# source_eagle.net
KiCad netlist of a schematic drawn in EAGLE
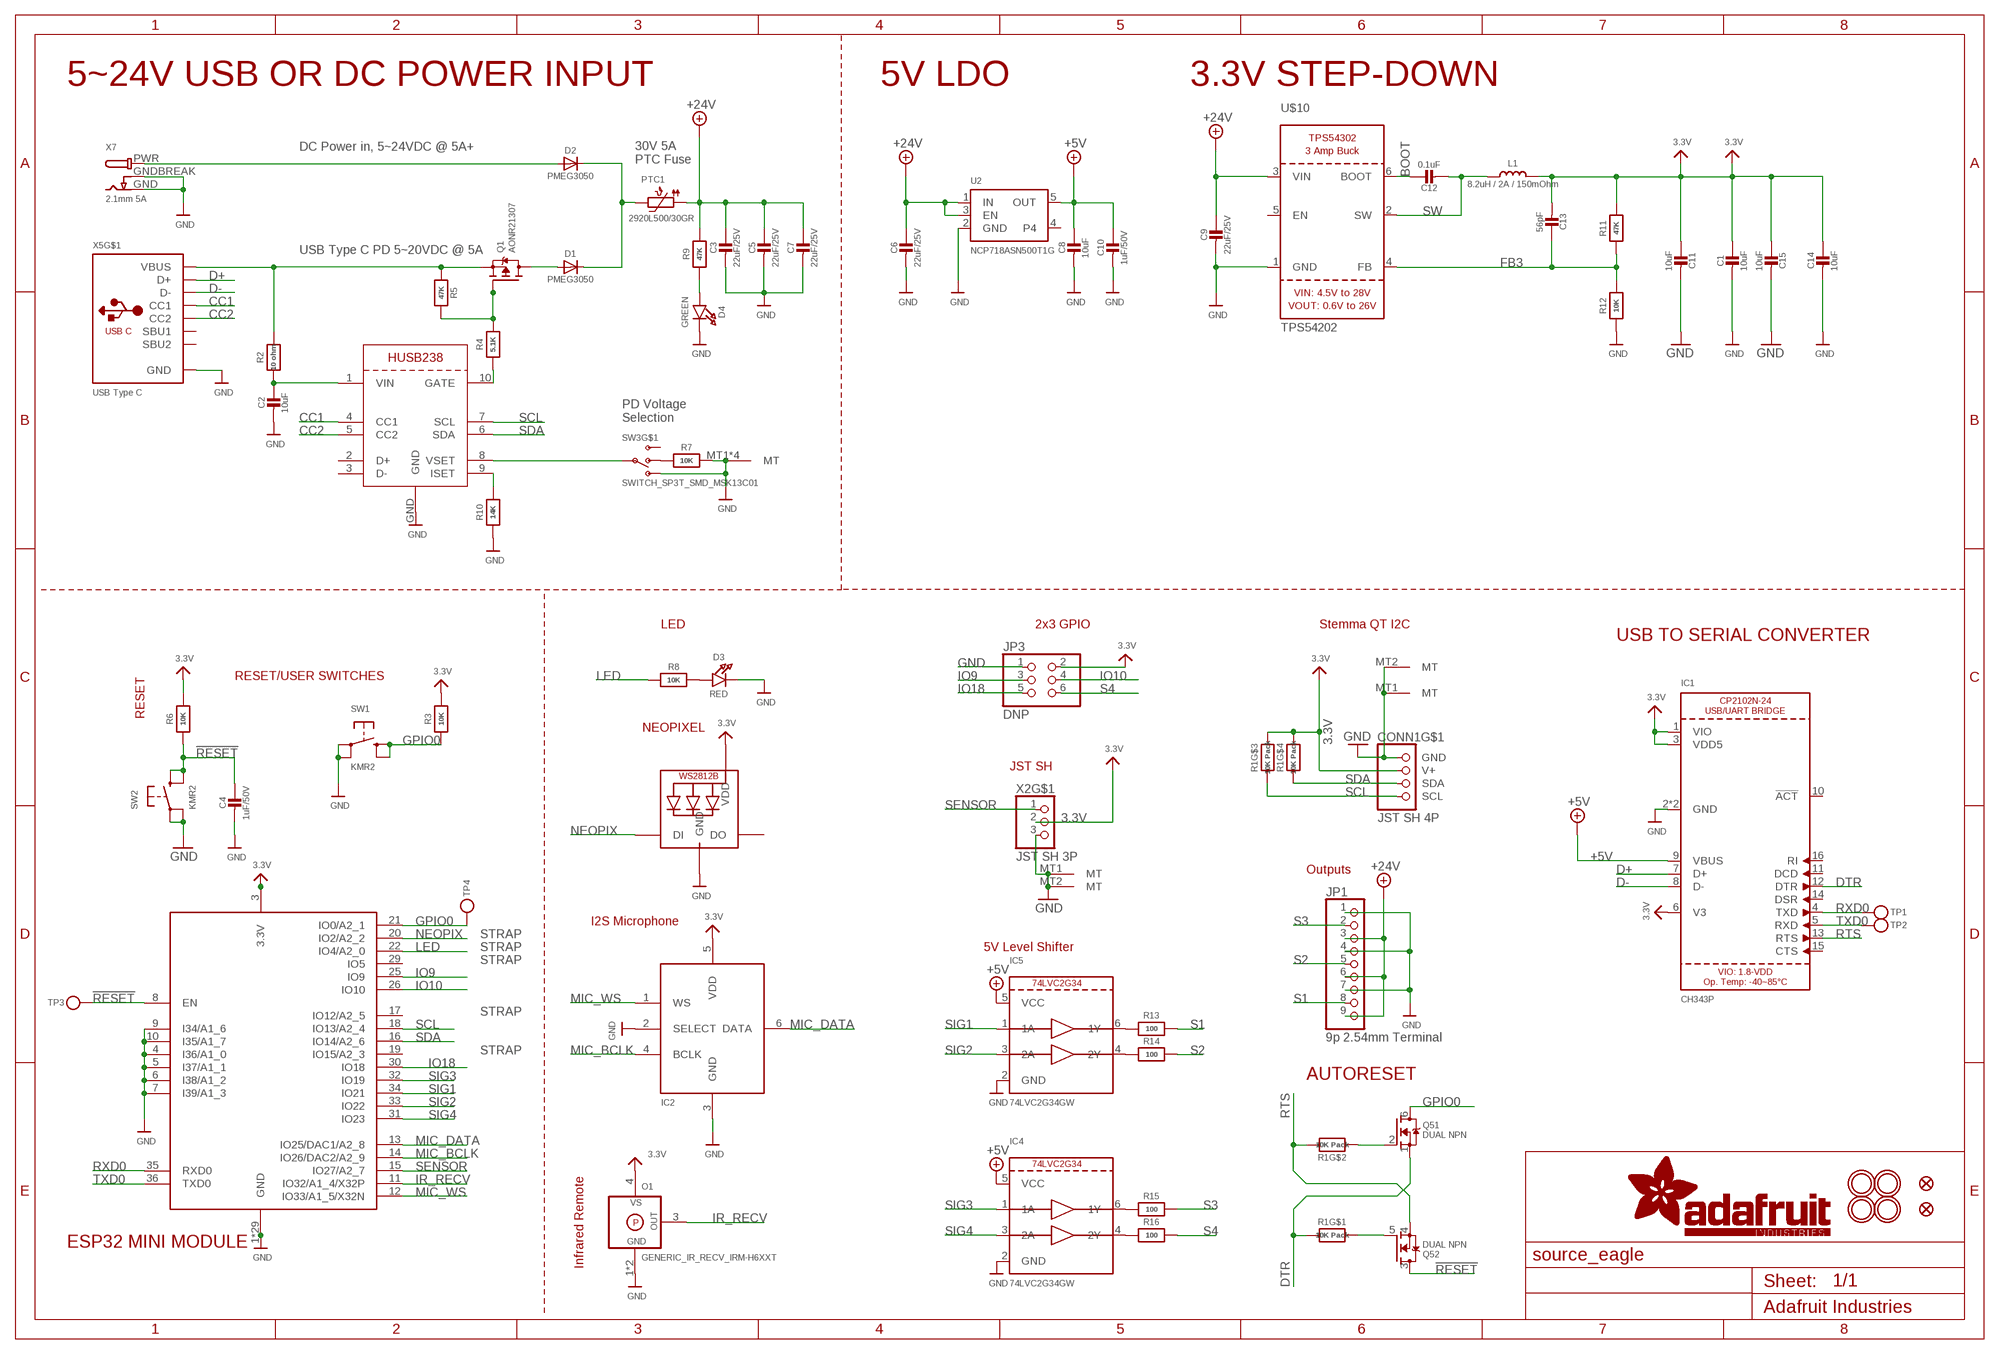
[diagram p0: schematic, sheet 1]

(export (version "E")
  (design (tool "Eeschema 10.0.6"))
  (components
    (comp (ref "C1")
      (value "10uF")
      (footprint "eagle-import:0805-NO")
      (libsource (lib "eagle-import") (part "CAP_CERAMIC0805-NOOUTLINE"))
    )
    (comp (ref "C2")
      (value "10uF")
      (footprint "eagle-import:0805-NO")
      (libsource (lib "eagle-import") (part "CAP_CERAMIC0805-NOOUTLINE"))
    )
    (comp (ref "C3")
      (value "22uF/25V")
      (footprint "eagle-import:0805-NO")
      (libsource (lib "eagle-import") (part "CAP_CERAMIC0805-NOOUTLINE"))
    )
    (comp (ref "C4")
      (value "1uF/50V")
      (footprint "eagle-import:0603-NO")
      (libsource (lib "eagle-import") (part "CAP_CERAMIC0603_NO"))
    )
    (comp (ref "C5")
      (value "22uF/25V")
      (footprint "eagle-import:0805-NO")
      (libsource (lib "eagle-import") (part "CAP_CERAMIC0805-NOOUTLINE"))
    )
    (comp (ref "C6")
      (value "22uF/25V")
      (footprint "eagle-import:0805-NO")
      (libsource (lib "eagle-import") (part "CAP_CERAMIC0805-NOOUTLINE"))
    )
    (comp (ref "C7")
      (value "22uF/25V")
      (footprint "eagle-import:0805-NO")
      (libsource (lib "eagle-import") (part "CAP_CERAMIC0805-NOOUTLINE"))
    )
    (comp (ref "C8")
      (value "10uF")
      (footprint "eagle-import:0805-NO")
      (fields (field (name "REV") "D"))
      (libsource (lib "eagle-import") (part "CAP_CERAMIC0805-NOOUTLINE"))
    )
    (comp (ref "C9")
      (value "22uF/25V")
      (footprint "eagle-import:0805-NO")
      (libsource (lib "eagle-import") (part "CAP_CERAMIC0805-NOOUTLINE"))
    )
    (comp (ref "C10")
      (value "1uF/50V")
      (footprint "eagle-import:0603-NO")
      (libsource (lib "eagle-import") (part "CAP_CERAMIC0603_NO"))
    )
    (comp (ref "C11")
      (value "10uF")
      (footprint "eagle-import:0805-NO")
      (libsource (lib "eagle-import") (part "CAP_CERAMIC0805-NOOUTLINE"))
    )
    (comp (ref "C12")
      (value "0.1uF")
      (footprint "eagle-import:0603-NO")
      (libsource (lib "eagle-import") (part "CAP_CERAMIC0603_NO"))
    )
    (comp (ref "C13")
      (value "56pF")
      (footprint "eagle-import:0603-NO")
      (libsource (lib "eagle-import") (part "CAP_CERAMIC0603_NO"))
    )
    (comp (ref "C14")
      (value "10uF")
      (footprint "eagle-import:0805-NO")
      (libsource (lib "eagle-import") (part "CAP_CERAMIC0805-NOOUTLINE"))
    )
    (comp (ref "C15")
      (value "10uF")
      (footprint "eagle-import:0805-NO")
      (libsource (lib "eagle-import") (part "CAP_CERAMIC0805-NOOUTLINE"))
    )
    (comp (ref "CONN1")
      (value "JST SH 4P")
      (footprint "eagle-import:JST_SH4")
      (libsource (lib "eagle-import") (part "STEMMA_I2C_QT"))
    )
    (comp (ref "D1")
      (value "PMEG3050")
      (footprint "eagle-import:SOD-128")
      (libsource (lib "eagle-import") (part "DIODE_SOD128"))
    )
    (comp (ref "D2")
      (value "PMEG3050")
      (footprint "eagle-import:SOD-128")
      (libsource (lib "eagle-import") (part "DIODE_SOD128"))
    )
    (comp (ref "D3")
      (value "RED")
      (footprint "eagle-import:CHIPLED_0603_NOOUTLINE")
      (libsource (lib "eagle-import") (part "LED0603_NOOUTLINE"))
    )
    (comp (ref "D4")
      (value "GREEN")
      (footprint "eagle-import:CHIPLED_0603_NOOUTLINE")
      (libsource (lib "eagle-import") (part "LED0603_NOOUTLINE"))
    )
    (comp (ref "IC1")
      (value "CH343P")
      (footprint "eagle-import:QFN16_3MM")
      (libsource (lib "eagle-import") (part "CH343P"))
    )
    (comp (ref "IC2")
      (value "ICS-43434")
      (footprint "eagle-import:SPH0645LM4H")
      (libsource (lib "eagle-import") (part "MIC_I2S_SPH0645"))
    )
    (comp (ref "IC4")
      (value "74LVC2G34GW")
      (footprint "eagle-import:SC70-6L")
      (libsource (lib "eagle-import") (part "74LVC2G34GW"))
    )
    (comp (ref "IC5")
      (value "74LVC2G34GW")
      (footprint "eagle-import:SC70-6L")
      (libsource (lib "eagle-import") (part "74LVC2G34GW"))
    )
    (comp (ref "JP1")
      (value "9p 2.54mm Terminal")
      (footprint "eagle-import:1X09_2.54MMTERMINAL")
      (libsource (lib "eagle-import") (part "HEADER-1X9_2.54MMTERM"))
    )
    (comp (ref "JP3")
      (value "DNP")
      (footprint "eagle-import:2X03_ROUND_70MIL")
      (libsource (lib "eagle-import") (part "HEADER-2X3"))
    )
    (comp (ref "L1")
      (value "8.2uH / 2A / 150mOhm")
      (footprint "eagle-import:INDUCTOR_5X5MM_NR5040_NOTHERMALS")
      (libsource (lib "eagle-import") (part "INDUCTORNR5040"))
    )
    (comp (ref "LED1")
      (value "WS2812B_SK6805_1515")
      (footprint "eagle-import:SK6805_1515")
      (libsource (lib "eagle-import") (part "WS2812B_SK6805_1515"))
    )
    (comp (ref "O1")
      (value "GENERIC_IR_RECV_IRM-H6XXT")
      (footprint "eagle-import:IRM-H6XXT")
      (libsource (lib "eagle-import") (part "GENERIC_IR_RECV_IRM-H6XXT"))
    )
    (comp (ref "PTC1")
      (value "2920L500/30GR")
      (footprint "eagle-import:PTC2920")
      (libsource (lib "eagle-import") (part "PTC_2920"))
    )
    (comp (ref "Q1")
      (value "AONR21307")
      (footprint "eagle-import:POWERDI3333")
      (libsource (lib "eagle-import") (part "MOSFET-P-POWERDI3333"))
    )
    (comp (ref "Q5")
      (value "DUAL NPN")
      (footprint "eagle-import:SOT363")
      (fields (field (name "JLC_ROTATION") "0"))
      (libsource (lib "eagle-import") (part "MOSFET-N_DUAL"))
    )
    (comp (ref "R1")
      (value "10K Pack")
      (footprint "eagle-import:RESPACK_4X0603")
      (libsource (lib "eagle-import") (part "RESISTOR_4PACK"))
    )
    (comp (ref "R2")
      (value "10 ohm")
      (footprint "eagle-import:0603-NO")
      (libsource (lib "eagle-import") (part "RESISTOR_0603_NOOUT"))
    )
    (comp (ref "R3")
      (value "10K")
      (footprint "eagle-import:0603-NO")
      (libsource (lib "eagle-import") (part "RESISTOR_0603_NOOUT"))
    )
    (comp (ref "R4")
      (value "5.1K")
      (footprint "eagle-import:0603-NO")
      (libsource (lib "eagle-import") (part "RESISTOR_0603_NOOUT"))
    )
    (comp (ref "R5")
      (value "47K")
      (footprint "eagle-import:0603-NO")
      (libsource (lib "eagle-import") (part "RESISTOR_0603_NOOUT"))
    )
    (comp (ref "R6")
      (value "10K")
      (footprint "eagle-import:0603-NO")
      (libsource (lib "eagle-import") (part "RESISTOR_0603_NOOUT"))
    )
    (comp (ref "R7")
      (value "10K")
      (footprint "eagle-import:0603-NO")
      (libsource (lib "eagle-import") (part "RESISTOR_0603_NOOUT"))
    )
    (comp (ref "R8")
      (value "10K")
      (footprint "eagle-import:0603-NO")
      (libsource (lib "eagle-import") (part "RESISTOR_0603_NOOUT"))
    )
    (comp (ref "R9")
      (value "47K")
      (footprint "eagle-import:0603-NO")
      (libsource (lib "eagle-import") (part "RESISTOR_0603_NOOUT"))
    )
    (comp (ref "R10")
      (value "14K")
      (footprint "eagle-import:0603-NO")
      (libsource (lib "eagle-import") (part "RESISTOR_0603_NOOUT"))
    )
    (comp (ref "R11")
      (value "47K")
      (footprint "eagle-import:0603-NO")
      (libsource (lib "eagle-import") (part "RESISTOR_0603_NOOUT"))
    )
    (comp (ref "R12")
      (value "10K")
      (footprint "eagle-import:0603-NO")
      (libsource (lib "eagle-import") (part "RESISTOR_0603_NOOUT"))
    )
    (comp (ref "R13")
      (value "100")
      (footprint "eagle-import:0603-NO")
      (libsource (lib "eagle-import") (part "RESISTOR_0603_NOOUT"))
    )
    (comp (ref "R14")
      (value "100")
      (footprint "eagle-import:0603-NO")
      (libsource (lib "eagle-import") (part "RESISTOR_0603_NOOUT"))
    )
    (comp (ref "R15")
      (value "100")
      (footprint "eagle-import:0603-NO")
      (libsource (lib "eagle-import") (part "RESISTOR_0603_NOOUT"))
    )
    (comp (ref "R16")
      (value "100")
      (footprint "eagle-import:0603-NO")
      (libsource (lib "eagle-import") (part "RESISTOR_0603_NOOUT"))
    )
    (comp (ref "SW1")
      (value "KMR2")
      (footprint "eagle-import:BTN_RKB2_4.6X2.8")
      (libsource (lib "eagle-import") (part "SWITCH_TACT_SMT_RKB2"))
    )
    (comp (ref "SW2")
      (value "KMR2")
      (footprint "eagle-import:BTN_RKB2_4.6X2.8")
      (libsource (lib "eagle-import") (part "SWITCH_TACT_SMT_RKB2"))
    )
    (comp (ref "SW3")
      (value "SWITCH_SP3T_SMD_MSK13C01")
      (footprint "eagle-import:MSK-13C01")
      (libsource (lib "eagle-import") (part "SWITCH_SP3T_SMD_MSK13C01"))
    )
    (comp (ref "TP1")
      (value "TESTPOINTROUND1.5MM")
      (footprint "eagle-import:TESTPOINT_ROUND_1.5MM")
      (libsource (lib "eagle-import") (part "TESTPOINTROUND1.5MM"))
    )
    (comp (ref "TP2")
      (value "TESTPOINTROUND1.5MM")
      (footprint "eagle-import:TESTPOINT_ROUND_1.5MM")
      (libsource (lib "eagle-import") (part "TESTPOINTROUND1.5MM"))
    )
    (comp (ref "TP3")
      (value "TESTPOINTROUND1.5MM")
      (footprint "eagle-import:TESTPOINT_ROUND_1.5MM")
      (libsource (lib "eagle-import") (part "TESTPOINTROUND1.5MM"))
    )
    (comp (ref "TP4")
      (value "TESTPOINTROUND1.5MM")
      (footprint "eagle-import:TESTPOINT_ROUND_1.5MM")
      (libsource (lib "eagle-import") (part "TESTPOINTROUND1.5MM"))
    )
    (comp (ref "U$10")
      (value "TPS54202")
      (footprint "eagle-import:SOT23-6")
      (libsource (lib "eagle-import") (part "TPS54302"))
    )
    (comp (ref "U$14")
      (value "MOUNTINGHOLE2.5")
      (footprint "eagle-import:MOUNTINGHOLE_2.5_PLATED")
      (libsource (lib "eagle-import") (part "MOUNTINGHOLE2.5"))
    )
    (comp (ref "U$20")
      (value "MOUNTINGHOLE2.5")
      (footprint "eagle-import:MOUNTINGHOLE_2.5_PLATED")
      (libsource (lib "eagle-import") (part "MOUNTINGHOLE2.5"))
    )
    (comp (ref "U$28")
      (value "MOUNTINGHOLE2.5")
      (footprint "eagle-import:MOUNTINGHOLE_2.5_PLATED")
      (libsource (lib "eagle-import") (part "MOUNTINGHOLE2.5"))
    )
    (comp (ref "U$31")
      (value "MOUNTINGHOLE2.5")
      (footprint "eagle-import:MOUNTINGHOLE_2.5_PLATED")
      (libsource (lib "eagle-import") (part "MOUNTINGHOLE2.5"))
    )
    (comp (ref "U$34")
      (value "FIDUCIAL_1MM")
      (footprint "eagle-import:FIDUCIAL_1MM")
      (libsource (lib "eagle-import") (part "FIDUCIAL_1MM"))
    )
    (comp (ref "U$35")
      (value "FIDUCIAL_1MM")
      (footprint "eagle-import:FIDUCIAL_1MM")
      (libsource (lib "eagle-import") (part "FIDUCIAL_1MM"))
    )
    (comp (ref "U2")
      (value "NCP718ASN500T1G")
      (footprint "eagle-import:SOT23-5")
      (fields (field (name "JLC_ROTATION") "0"))
      (libsource (lib "eagle-import") (part "VREG_SOT23-5"))
    )
    (comp (ref "X2")
      (value "JST SH 3P")
      (footprint "eagle-import:JST_SH3")
      (libsource (lib "eagle-import") (part "CON_JST_SH_3PINHORZ"))
    )
    (comp (ref "X3")
      (value "HUSB238")
      (footprint "eagle-import:DFN10_3X3MM")
      (libsource (lib "eagle-import") (part "HUSB238"))
    )
    (comp (ref "X4")
      (value "ESP32-MINI-1")
      (footprint "eagle-import:ESP32-MINI-1")
      (libsource (lib "eagle-import") (part "ESP32-MINI-1"))
    )
    (comp (ref "X5")
      (value "USB Type C")
      (footprint "eagle-import:USB_C_CUSB31-CFM2AX-01-X")
      (libsource (lib "eagle-import") (part "USB_C"))
    )
    (comp (ref "X7")
      (value "2.1mm 5A")
      (footprint "eagle-import:DCJACK_2MM_PTH")
      (libsource (lib "eagle-import") (part "DCBARRELPTH"))
    )
  )
  (nets
    (net (code "1") (name "+5V") (class "Default")
      (node (ref "C10") (pin "1") (pinfunction "1_1") (pintype "passive"))
      (node (ref "C8") (pin "1") (pinfunction "1_1") (pintype "passive"))
      (node (ref "IC1") (pin "9") (pinfunction "VBUS_9") (pintype "power_in"))
      (node (ref "IC4") (pin "5") (pinfunction "VCC_5") (pintype "power_in"))
      (node (ref "IC5") (pin "5") (pinfunction "VCC_5") (pintype "power_in"))
      (node (ref "U2") (pin "5") (pinfunction "OUT_5") (pintype "power_in"))
    )
    (net (code "2") (name "+24V") (class "Default")
      (node (ref "C3") (pin "1") (pinfunction "1_1") (pintype "passive"))
      (node (ref "C5") (pin "1") (pinfunction "1_1") (pintype "passive"))
      (node (ref "C6") (pin "1") (pinfunction "1_1") (pintype "passive"))
      (node (ref "C7") (pin "1") (pinfunction "1_1") (pintype "passive"))
      (node (ref "C9") (pin "1") (pinfunction "1_1") (pintype "passive"))
      (node (ref "JP1") (pin "3") (pinfunction "3_3") (pintype "passive"))
      (node (ref "JP1") (pin "6") (pinfunction "6_6") (pintype "passive"))
      (node (ref "JP1") (pin "9") (pinfunction "9_9") (pintype "passive"))
      (node (ref "PTC1") (pin "P$1") (pinfunction "1_P$1") (pintype "passive"))
      (node (ref "R9") (pin "2") (pinfunction "2_2") (pintype "passive"))
      (node (ref "U$10") (pin "3") (pinfunction "VIN_3") (pintype "power_in"))
      (node (ref "U2") (pin "1") (pinfunction "IN_1") (pintype "power_in"))
      (node (ref "U2") (pin "3") (pinfunction "EN_3") (pintype "input"))
    )
    (net (code "3") (name "/BOOT") (class "Default")
      (node (ref "C12") (pin "1") (pinfunction "1_1") (pintype "passive"))
      (node (ref "U$10") (pin "6") (pinfunction "BOOT_6") (pintype "passive"))
    )
    (net (code "4") (name "/CC1") (class "Default")
      (node (ref "X3") (pin "4") (pinfunction "CC1_4") (pintype "input"))
      (node (ref "X5") (pin "A5") (pinfunction "CC1_A5") (pintype "bidirectional"))
    )
    (net (code "5") (name "/CC2") (class "Default")
      (node (ref "X3") (pin "5") (pinfunction "CC2_5") (pintype "input"))
      (node (ref "X5") (pin "B5") (pinfunction "CC2_B5") (pintype "bidirectional"))
    )
    (net (code "6") (name "/D+") (class "Default")
      (node (ref "IC1") (pin "7") (pinfunction "D+_7") (pintype "bidirectional"))
      (node (ref "X5") (pin "A6") (pinfunction "D+_A6") (pintype "bidirectional"))
      (node (ref "X5") (pin "B6") (pinfunction "D+_B6") (pintype "bidirectional"))
    )
    (net (code "7") (name "/D-") (class "Default")
      (node (ref "IC1") (pin "8") (pinfunction "D-_8") (pintype "bidirectional"))
      (node (ref "X5") (pin "A7") (pinfunction "D-_A7") (pintype "bidirectional"))
      (node (ref "X5") (pin "B7") (pinfunction "D-_B7") (pintype "bidirectional"))
    )
    (net (code "8") (name "/DTR") (class "Default")
      (node (ref "IC1") (pin "12") (pinfunction "DTR_12") (pintype "output"))
      (node (ref "Q5") (pin "1") (pinfunction "S_1") (pintype "bidirectional"))
      (node (ref "R1") (pin "1") (pinfunction "1_1") (pintype "passive"))
    )
    (net (code "9") (name "/FB3") (class "Default")
      (node (ref "C13") (pin "1") (pinfunction "1_1") (pintype "passive"))
      (node (ref "R11") (pin "1") (pinfunction "1_1") (pintype "passive"))
      (node (ref "R12") (pin "2") (pinfunction "2_2") (pintype "passive"))
      (node (ref "U$10") (pin "4") (pinfunction "FB_4") (pintype "input"))
    )
    (net (code "10") (name "/GPIO0") (class "Default")
      (node (ref "Q5") (pin "6") (pinfunction "D_6") (pintype "bidirectional"))
      (node (ref "R3") (pin "1") (pinfunction "1_1") (pintype "passive"))
      (node (ref "SW1") (pin "B") (pinfunction "S_B") (pintype "passive"))
      (node (ref "SW1") (pin "B'") (pinfunction "S1_B'") (pintype "passive"))
      (node (ref "TP4") (pin "P$1") (pinfunction "P$1_P$1") (pintype "bidirectional"))
      (node (ref "X4") (pin "21") (pinfunction "IO0/A2_1_21") (pintype "bidirectional"))
    )
    (net (code "11") (name "/IO9") (class "Default")
      (node (ref "JP3") (pin "3") (pinfunction "3_3") (pintype "passive"))
      (node (ref "X4") (pin "25") (pinfunction "IO9_25") (pintype "bidirectional"))
    )
    (net (code "12") (name "/IO10") (class "Default")
      (node (ref "JP3") (pin "4") (pinfunction "4_4") (pintype "passive"))
      (node (ref "X4") (pin "26") (pinfunction "IO10_26") (pintype "bidirectional"))
    )
    (net (code "13") (name "/IO18") (class "Default")
      (node (ref "JP3") (pin "5") (pinfunction "5_5") (pintype "passive"))
      (node (ref "X4") (pin "30") (pinfunction "IO18_30") (pintype "bidirectional"))
    )
    (net (code "14") (name "/IR_RECV") (class "Default")
      (node (ref "O1") (pin "3") (pinfunction "OUT_3") (pintype "output"))
      (node (ref "X4") (pin "11") (pinfunction "IO32/A1_4/X32P_11") (pintype "bidirectional"))
    )
    (net (code "15") (name "/LED") (class "Default")
      (node (ref "R8") (pin "1") (pinfunction "1_1") (pintype "passive"))
      (node (ref "X4") (pin "22") (pinfunction "IO4/A2_0_22") (pintype "bidirectional"))
    )
    (net (code "16") (name "/MIC_BCLK") (class "Default")
      (node (ref "IC2") (pin "4") (pinfunction "BCLK_4") (pintype "input"))
      (node (ref "X4") (pin "14") (pinfunction "IO26/DAC2/A2_9_14") (pintype "bidirectional"))
    )
    (net (code "17") (name "/MIC_DATA") (class "Default")
      (node (ref "IC2") (pin "6") (pinfunction "DATA_6") (pintype "output"))
      (node (ref "X4") (pin "13") (pinfunction "IO25/DAC1/A2_8_13") (pintype "bidirectional"))
    )
    (net (code "18") (name "/MIC_WS") (class "Default")
      (node (ref "IC2") (pin "1") (pinfunction "WS_1") (pintype "input"))
      (node (ref "X4") (pin "12") (pinfunction "IO33/A1_5/X32N_12") (pintype "bidirectional"))
    )
    (net (code "19") (name "/NEOPIX") (class "Default")
      (node (ref "LED1") (pin "1") (pinfunction "DI_1") (pintype "input"))
      (node (ref "X4") (pin "20") (pinfunction "IO2/A2_2_20") (pintype "bidirectional"))
    )
    (net (code "20") (name "/RTS") (class "Default")
      (node (ref "IC1") (pin "13") (pinfunction "RTS_13") (pintype "output"))
      (node (ref "Q5") (pin "4") (pinfunction "S_4") (pintype "bidirectional"))
      (node (ref "R1") (pin "7") (pinfunction "2_7") (pintype "passive"))
    )
    (net (code "21") (name "/RXD0") (class "Default")
      (node (ref "IC1") (pin "4") (pinfunction "TXD_4") (pintype "output"))
      (node (ref "TP1") (pin "P$1") (pinfunction "P$1_P$1") (pintype "bidirectional"))
      (node (ref "X4") (pin "35") (pinfunction "RXD0_35") (pintype "input"))
    )
    (net (code "22") (name "/S1") (class "Default")
      (node (ref "JP1") (pin "8") (pinfunction "8_8") (pintype "passive"))
      (node (ref "R13") (pin "2") (pinfunction "2_2") (pintype "passive"))
    )
    (net (code "23") (name "/S2") (class "Default")
      (node (ref "JP1") (pin "5") (pinfunction "5_5") (pintype "passive"))
      (node (ref "R14") (pin "2") (pinfunction "2_2") (pintype "passive"))
    )
    (net (code "24") (name "/S3") (class "Default")
      (node (ref "JP1") (pin "2") (pinfunction "2_2") (pintype "passive"))
      (node (ref "R15") (pin "2") (pinfunction "2_2") (pintype "passive"))
    )
    (net (code "25") (name "/S4") (class "Default")
      (node (ref "JP3") (pin "6") (pinfunction "6_6") (pintype "passive"))
      (node (ref "R16") (pin "2") (pinfunction "2_2") (pintype "passive"))
    )
    (net (code "26") (name "/SCL") (class "Default")
      (node (ref "CONN1") (pin "4") (pinfunction "SCL_4") (pintype "passive"))
      (node (ref "R1") (pin "3") (pinfunction "1_3") (pintype "passive"))
      (node (ref "X3") (pin "7") (pinfunction "SCL_7") (pintype "bidirectional"))
      (node (ref "X4") (pin "18") (pinfunction "IO13/A2_4_18") (pintype "bidirectional"))
    )
    (net (code "27") (name "/SDA") (class "Default")
      (node (ref "CONN1") (pin "3") (pinfunction "SDA_3") (pintype "passive"))
      (node (ref "R1") (pin "4") (pinfunction "1_4") (pintype "passive"))
      (node (ref "X3") (pin "6") (pinfunction "SDA_6") (pintype "bidirectional"))
      (node (ref "X4") (pin "16") (pinfunction "IO14/A2_6_16") (pintype "bidirectional"))
    )
    (net (code "28") (name "/SENSOR") (class "Default")
      (node (ref "X2") (pin "1") (pinfunction "1_1") (pintype "passive"))
      (node (ref "X4") (pin "15") (pinfunction "IO27/A2_7_15") (pintype "bidirectional"))
    )
    (net (code "29") (name "/SIG1") (class "Default")
      (node (ref "IC5") (pin "1") (pinfunction "1A_1") (pintype "input"))
      (node (ref "X4") (pin "34") (pinfunction "IO21_34") (pintype "bidirectional"))
    )
    (net (code "30") (name "/SIG2") (class "Default")
      (node (ref "IC5") (pin "3") (pinfunction "2A_3") (pintype "input"))
      (node (ref "X4") (pin "33") (pinfunction "IO22_33") (pintype "bidirectional"))
    )
    (net (code "31") (name "/SIG3") (class "Default")
      (node (ref "IC4") (pin "1") (pinfunction "1A_1") (pintype "input"))
      (node (ref "X4") (pin "32") (pinfunction "IO19_32") (pintype "bidirectional"))
    )
    (net (code "32") (name "/SIG4") (class "Default")
      (node (ref "IC4") (pin "3") (pinfunction "2A_3") (pintype "input"))
      (node (ref "X4") (pin "31") (pinfunction "IO23_31") (pintype "bidirectional"))
    )
    (net (code "33") (name "/SW") (class "Default")
      (node (ref "C12") (pin "2") (pinfunction "2_2") (pintype "passive"))
      (node (ref "L1") (pin "P$1") (pinfunction "1_P$1") (pintype "passive"))
      (node (ref "U$10") (pin "2") (pinfunction "SW_2") (pintype "power_in"))
    )
    (net (code "34") (name "/TXD0") (class "Default")
      (node (ref "IC1") (pin "5") (pinfunction "RXD_5") (pintype "input"))
      (node (ref "TP2") (pin "P$1") (pinfunction "P$1_P$1") (pintype "bidirectional"))
      (node (ref "X4") (pin "36") (pinfunction "TXD0_36") (pintype "output"))
    )
    (net (code "35") (name "/~{RESET}") (class "Default")
      (node (ref "C4") (pin "1") (pinfunction "1_1") (pintype "passive"))
      (node (ref "Q5") (pin "3") (pinfunction "D_3") (pintype "bidirectional"))
      (node (ref "R6") (pin "1") (pinfunction "1_1") (pintype "passive"))
      (node (ref "SW2") (pin "B") (pinfunction "S_B") (pintype "passive"))
      (node (ref "SW2") (pin "B'") (pinfunction "S1_B'") (pintype "passive"))
      (node (ref "TP3") (pin "P$1") (pinfunction "P$1_P$1") (pintype "bidirectional"))
      (node (ref "X4") (pin "8") (pinfunction "EN_8") (pintype "input"))
    )
    (net (code "36") (name "3.3V") (class "Default")
      (node (ref "C1") (pin "1") (pinfunction "1_1") (pintype "passive"))
      (node (ref "C11") (pin "1") (pinfunction "1_1") (pintype "passive"))
      (node (ref "C13") (pin "2") (pinfunction "2_2") (pintype "passive"))
      (node (ref "C14") (pin "1") (pinfunction "1_1") (pintype "passive"))
      (node (ref "C15") (pin "1") (pinfunction "1_1") (pintype "passive"))
      (node (ref "CONN1") (pin "2") (pinfunction "V+_2") (pintype "passive"))
      (node (ref "IC1") (pin "1") (pinfunction "VIO_1") (pintype "power_in"))
      (node (ref "IC1") (pin "3") (pinfunction "VDD5_3") (pintype "power_in"))
      (node (ref "IC1") (pin "6") (pinfunction "V3_6") (pintype "passive"))
      (node (ref "IC2") (pin "5") (pinfunction "VDD_5") (pintype "power_in"))
      (node (ref "JP3") (pin "2") (pinfunction "2_2") (pintype "passive"))
      (node (ref "L1") (pin "P$2") (pinfunction "2_P$2") (pintype "passive"))
      (node (ref "LED1") (pin "2") (pinfunction "VDD_2") (pintype "power_in"))
      (node (ref "O1") (pin "4") (pinfunction "VS_4") (pintype "power_in"))
      (node (ref "R1") (pin "5") (pinfunction "2_5") (pintype "passive"))
      (node (ref "R1") (pin "6") (pinfunction "2_6") (pintype "passive"))
      (node (ref "R11") (pin "2") (pinfunction "2_2") (pintype "passive"))
      (node (ref "R3") (pin "2") (pinfunction "2_2") (pintype "passive"))
      (node (ref "R6") (pin "2") (pinfunction "2_2") (pintype "passive"))
      (node (ref "X2") (pin "2") (pinfunction "2_2") (pintype "passive"))
      (node (ref "X4") (pin "3") (pinfunction "3.3V_3") (pintype "passive"))
    )
    (net (code "37") (name "GND") (class "Default")
      (node (ref "C1") (pin "2") (pinfunction "2_2") (pintype "passive"))
      (node (ref "C10") (pin "2") (pinfunction "2_2") (pintype "passive"))
      (node (ref "C11") (pin "2") (pinfunction "2_2") (pintype "passive"))
      (node (ref "C14") (pin "2") (pinfunction "2_2") (pintype "passive"))
      (node (ref "C15") (pin "2") (pinfunction "2_2") (pintype "passive"))
      (node (ref "C2") (pin "2") (pinfunction "2_2") (pintype "passive"))
      (node (ref "C3") (pin "2") (pinfunction "2_2") (pintype "passive"))
      (node (ref "C4") (pin "2") (pinfunction "2_2") (pintype "passive"))
      (node (ref "C5") (pin "2") (pinfunction "2_2") (pintype "passive"))
      (node (ref "C6") (pin "2") (pinfunction "2_2") (pintype "passive"))
      (node (ref "C7") (pin "2") (pinfunction "2_2") (pintype "passive"))
      (node (ref "C8") (pin "2") (pinfunction "2_2") (pintype "passive"))
      (node (ref "C9") (pin "2") (pinfunction "2_2") (pintype "passive"))
      (node (ref "CONN1") (pin "1") (pinfunction "GND_1") (pintype "passive"))
      (node (ref "CONN1") (pin "MT1") (pinfunction "MT_MT1") (pintype "bidirectional"))
      (node (ref "CONN1") (pin "MT2") (pinfunction "MT_MT2") (pintype "bidirectional"))
      (node (ref "D3") (pin "C") (pinfunction "C_C") (pintype "passive"))
      (node (ref "D4") (pin "C") (pinfunction "C_C") (pintype "passive"))
      (node (ref "IC1") (pin "2") (pinfunction "GND_2") (pintype "power_in"))
      (node (ref "IC1") (pin "THERMAL") (pinfunction "GND_THERMAL") (pintype "power_in"))
      (node (ref "IC2") (pin "2") (pinfunction "SELECT_2") (pintype "input"))
      (node (ref "IC2") (pin "3") (pinfunction "GND_3") (pintype "power_in"))
      (node (ref "IC4") (pin "2") (pinfunction "GND_2") (pintype "power_in"))
      (node (ref "IC5") (pin "2") (pinfunction "GND_2") (pintype "power_in"))
      (node (ref "JP1") (pin "1") (pinfunction "1_1") (pintype "passive"))
      (node (ref "JP1") (pin "4") (pinfunction "4_4") (pintype "passive"))
      (node (ref "JP1") (pin "7") (pinfunction "7_7") (pintype "passive"))
      (node (ref "JP3") (pin "1") (pinfunction "1_1") (pintype "passive"))
      (node (ref "LED1") (pin "4") (pinfunction "GND_4") (pintype "power_in"))
      (node (ref "O1") (pin "1") (pinfunction "GND_1") (pintype "power_in"))
      (node (ref "O1") (pin "2") (pinfunction "GND_2") (pintype "power_in"))
      (node (ref "R10") (pin "1") (pinfunction "1_1") (pintype "passive"))
      (node (ref "R12") (pin "1") (pinfunction "1_1") (pintype "passive"))
      (node (ref "R7") (pin "1") (pinfunction "1_1") (pintype "passive"))
      (node (ref "SW1") (pin "A") (pinfunction "P_A") (pintype "passive"))
      (node (ref "SW1") (pin "A'") (pinfunction "P1_A'") (pintype "passive"))
      (node (ref "SW2") (pin "A") (pinfunction "P_A") (pintype "passive"))
      (node (ref "SW2") (pin "A'") (pinfunction "P1_A'") (pintype "passive"))
      (node (ref "SW3") (pin "4") (pinfunction "3_4") (pintype "passive"))
      (node (ref "SW3") (pin "MT1") (pinfunction "MT_MT1") (pintype "bidirectional"))
      (node (ref "SW3") (pin "MT2") (pinfunction "MT_MT2") (pintype "bidirectional"))
      (node (ref "SW3") (pin "MT3") (pinfunction "MT_MT3") (pintype "bidirectional"))
      (node (ref "SW3") (pin "MT4") (pinfunction "MT_MT4") (pintype "bidirectional"))
      (node (ref "U$10") (pin "1") (pinfunction "GND_1") (pintype "power_in"))
      (node (ref "U2") (pin "2") (pinfunction "GND_2") (pintype "power_in"))
      (node (ref "X2") (pin "3") (pinfunction "3_3") (pintype "passive"))
      (node (ref "X2") (pin "MT1") (pinfunction "MT_MT1") (pintype "bidirectional"))
      (node (ref "X2") (pin "MT2") (pinfunction "MT_MT2") (pintype "bidirectional"))
      (node (ref "X3") (pin "GND") (pinfunction "GND_GND") (pintype "power_in"))
      (node (ref "X4") (pin "1") (pinfunction "GND_1") (pintype "passive"))
      (node (ref "X4") (pin "10") (pinfunction "I35/A1_7_10") (pintype "input"))
      (node (ref "X4") (pin "2") (pinfunction "GND_2") (pintype "passive"))
      (node (ref "X4") (pin "27") (pinfunction "GND_27") (pintype "passive"))
      (node (ref "X4") (pin "38") (pinfunction "GND_38") (pintype "passive"))
      (node (ref "X4") (pin "39") (pinfunction "GND_39") (pintype "passive"))
      (node (ref "X4") (pin "4") (pinfunction "I36/A1_0_4") (pintype "input"))
      (node (ref "X4") (pin "40") (pinfunction "GND_40") (pintype "passive"))
      (node (ref "X4") (pin "41") (pinfunction "GND_41") (pintype "passive"))
      (node (ref "X4") (pin "42") (pinfunction "GND_42") (pintype "passive"))
      (node (ref "X4") (pin "43") (pinfunction "GND_43") (pintype "passive"))
      (node (ref "X4") (pin "44") (pinfunction "GND_44") (pintype "passive"))
      (node (ref "X4") (pin "45") (pinfunction "GND_45") (pintype "passive"))
      (node (ref "X4") (pin "46") (pinfunction "GND_46") (pintype "passive"))
      (node (ref "X4") (pin "47") (pinfunction "GND_47") (pintype "passive"))
      (node (ref "X4") (pin "48") (pinfunction "GND_48") (pintype "passive"))
      (node (ref "X4") (pin "49") (pinfunction "GND_49") (pintype "passive"))
      (node (ref "X4") (pin "5") (pinfunction "I37/A1_1_5") (pintype "input"))
      (node (ref "X4") (pin "50") (pinfunction "GND_50") (pintype "passive"))
      (node (ref "X4") (pin "51") (pinfunction "GND_51") (pintype "passive"))
      (node (ref "X4") (pin "52") (pinfunction "GND_52") (pintype "passive"))
      (node (ref "X4") (pin "53") (pinfunction "GND_53") (pintype "passive"))
      (node (ref "X4") (pin "54") (pinfunction "GND_54") (pintype "passive"))
      (node (ref "X4") (pin "55") (pinfunction "GND_55") (pintype "passive"))
      (node (ref "X4") (pin "56") (pinfunction "GND_56") (pintype "passive"))
      (node (ref "X4") (pin "57") (pinfunction "GND_57") (pintype "passive"))
      (node (ref "X4") (pin "58") (pinfunction "GND_58") (pintype "passive"))
      (node (ref "X4") (pin "59") (pinfunction "GND_59") (pintype "passive"))
      (node (ref "X4") (pin "6") (pinfunction "I38/A1_2_6") (pintype "input"))
      (node (ref "X4") (pin "60") (pinfunction "GND_60") (pintype "passive"))
      (node (ref "X4") (pin "61") (pinfunction "GND_61") (pintype "passive"))
      (node (ref "X4") (pin "62") (pinfunction "GND_62") (pintype "passive"))
      (node (ref "X4") (pin "63") (pinfunction "GND_63") (pintype "passive"))
      (node (ref "X4") (pin "7") (pinfunction "I39/A1_3_7") (pintype "input"))
      (node (ref "X4") (pin "9") (pinfunction "I34/A1_6_9") (pintype "input"))
      (node (ref "X5") (pin "A1B12") (pinfunction "GND_A1B12") (pintype "power_in"))
      (node (ref "X5") (pin "B1A12") (pinfunction "GND_B1A12") (pintype "power_in"))
      (node (ref "X7") (pin "GND") (pinfunction "GND_GND") (pintype "power_in"))
      (node (ref "X7") (pin "GNDBREAK") (pinfunction "GNDBREAK_GNDBREAK") (pintype "power_in"))
    )
    (net (code "38") (name "Net-(D2-PadA)") (class "Default")
      (node (ref "D2") (pin "A") (pinfunction "A_A") (pintype "passive"))
      (node (ref "X7") (pin "PWR") (pinfunction "PWR_PWR") (pintype "power_in"))
    )
    (net (code "39") (name "Net-(D3-PadA)") (class "Default")
      (node (ref "D3") (pin "A") (pinfunction "A_A") (pintype "passive"))
      (node (ref "R8") (pin "2") (pinfunction "2_2") (pintype "passive"))
    )
    (net (code "40") (name "Net-(D4-PadA)") (class "Default")
      (node (ref "D4") (pin "A") (pinfunction "A_A") (pintype "passive"))
      (node (ref "R9") (pin "1") (pinfunction "1_1") (pintype "passive"))
    )
    (net (code "41") (name "Net-(IC4-1Y)") (class "Default")
      (node (ref "IC4") (pin "6") (pinfunction "1Y_6") (pintype "output"))
      (node (ref "R15") (pin "1") (pinfunction "1_1") (pintype "passive"))
    )
    (net (code "42") (name "Net-(IC4-2Y)") (class "Default")
      (node (ref "IC4") (pin "4") (pinfunction "2Y_4") (pintype "output"))
      (node (ref "R16") (pin "1") (pinfunction "1_1") (pintype "passive"))
    )
    (net (code "43") (name "Net-(IC5-1Y)") (class "Default")
      (node (ref "IC5") (pin "6") (pinfunction "1Y_6") (pintype "output"))
      (node (ref "R13") (pin "1") (pinfunction "1_1") (pintype "passive"))
    )
    (net (code "44") (name "Net-(IC5-2Y)") (class "Default")
      (node (ref "IC5") (pin "4") (pinfunction "2Y_4") (pintype "output"))
      (node (ref "R14") (pin "1") (pinfunction "1_1") (pintype "passive"))
    )
    (net (code "45") (name "Net-(PTC1-2)") (class "Default")
      (node (ref "D1") (pin "C") (pinfunction "C_C") (pintype "passive"))
      (node (ref "D2") (pin "C") (pinfunction "C_C") (pintype "passive"))
      (node (ref "PTC1") (pin "P$2") (pinfunction "2_P$2") (pintype "passive"))
    )
    (net (code "46") (name "Net-(Q1-D)") (class "Default")
      (node (ref "D1") (pin "A") (pinfunction "A_A") (pintype "passive"))
      (node (ref "Q1") (pin "5678") (pinfunction "D_5678") (pintype "passive"))
    )
    (net (code "47") (name "Net-(Q1-G)") (class "Default")
      (node (ref "Q1") (pin "4") (pinfunction "G_4") (pintype "passive"))
      (node (ref "R4") (pin "2") (pinfunction "2_2") (pintype "passive"))
      (node (ref "R5") (pin "2") (pinfunction "2_2") (pintype "passive"))
    )
    (net (code "48") (name "Net-(Q1-S-Pad1)") (class "Default")
      (node (ref "Q1") (pin "1") (pinfunction "S_1") (pintype "passive"))
      (node (ref "Q1") (pin "2") (pinfunction "S_2") (pintype "passive"))
      (node (ref "Q1") (pin "3") (pinfunction "S_3") (pintype "passive"))
      (node (ref "R2") (pin "2") (pinfunction "2_2") (pintype "passive"))
      (node (ref "R5") (pin "1") (pinfunction "1_1") (pintype "passive"))
      (node (ref "X5") (pin "A4B9") (pinfunction "VBUS_A4B9") (pintype "power_in"))
      (node (ref "X5") (pin "B4A9") (pinfunction "VBUS_B4A9") (pintype "power_in"))
    )
    (net (code "49") (name "Net-(Q5A-G)") (class "Default")
      (node (ref "Q5") (pin "2") (pinfunction "G_2") (pintype "bidirectional"))
      (node (ref "R1") (pin "2") (pinfunction "1_2") (pintype "passive"))
    )
    (net (code "50") (name "Net-(Q5B-G)") (class "Default")
      (node (ref "Q5") (pin "5") (pinfunction "G_5") (pintype "bidirectional"))
      (node (ref "R1") (pin "8") (pinfunction "2_8") (pintype "passive"))
    )
    (net (code "51") (name "Net-(R7-Pad2)") (class "Default")
      (node (ref "R7") (pin "2") (pinfunction "2_2") (pintype "passive"))
      (node (ref "SW3") (pin "2") (pinfunction "2_2") (pintype "passive"))
    )
    (net (code "52") (name "Net-(SW3A-P)") (class "Default")
      (node (ref "SW3") (pin "3") (pinfunction "P_3") (pintype "passive"))
      (node (ref "X3") (pin "8") (pinfunction "VSET_8") (pintype "passive"))
    )
    (net (code "53") (name "Net-(X3-GATE)") (class "Default")
      (node (ref "R4") (pin "1") (pinfunction "1_1") (pintype "passive"))
      (node (ref "X3") (pin "10") (pinfunction "GATE_10") (pintype "output"))
    )
    (net (code "54") (name "Net-(X3-ISET)") (class "Default")
      (node (ref "R10") (pin "2") (pinfunction "2_2") (pintype "passive"))
      (node (ref "X3") (pin "9") (pinfunction "ISET_9") (pintype "passive"))
    )
    (net (code "55") (name "Net-(X3-VIN)") (class "Default")
      (node (ref "C2") (pin "1") (pinfunction "1_1") (pintype "passive"))
      (node (ref "R2") (pin "1") (pinfunction "1_1") (pintype "passive"))
      (node (ref "X3") (pin "1") (pinfunction "VIN_1") (pintype "power_in"))
    )
    (net (code "56") (name "unconnected-(IC1-CTS-Pad15)") (class "Default")
      (node (ref "IC1") (pin "15") (pinfunction "CTS_15") (pintype "input"))
    )
    (net (code "57") (name "unconnected-(IC1-DCD-Pad11)") (class "Default")
      (node (ref "IC1") (pin "11") (pinfunction "DCD_11") (pintype "input"))
    )
    (net (code "58") (name "unconnected-(IC1-DSR-Pad14)") (class "Default")
      (node (ref "IC1") (pin "14") (pinfunction "DSR_14") (pintype "input"))
    )
    (net (code "59") (name "unconnected-(IC1-RI-Pad16)") (class "Default")
      (node (ref "IC1") (pin "16") (pinfunction "RI_16") (pintype "input"))
    )
    (net (code "60") (name "unconnected-(IC1-~{ACT}-Pad10)") (class "Default")
      (node (ref "IC1") (pin "10") (pinfunction "~{ACT}_10") (pintype "bidirectional"))
    )
    (net (code "61") (name "unconnected-(LED1-DO-Pad3)") (class "Default")
      (node (ref "LED1") (pin "3") (pinfunction "DO_3") (pintype "output"))
    )
    (net (code "62") (name "unconnected-(SW3-Pad1)") (class "Default")
      (node (ref "SW3") (pin "1") (pinfunction "1_1") (pintype "passive"))
    )
    (net (code "63") (name "unconnected-(U$10-EN-Pad5)") (class "Default")
      (node (ref "U$10") (pin "5") (pinfunction "EN_5") (pintype "input"))
    )
    (net (code "64") (name "unconnected-(U2-P4-Pad4)") (class "Default")
      (node (ref "U2") (pin "4") (pinfunction "P4_4") (pintype "bidirectional"))
    )
    (net (code "65") (name "unconnected-(X3-D+-Pad2)") (class "Default")
      (node (ref "X3") (pin "2") (pinfunction "D+_2") (pintype "input"))
    )
    (net (code "66") (name "unconnected-(X3-D--Pad3)") (class "Default")
      (node (ref "X3") (pin "3") (pinfunction "D-_3") (pintype "input"))
    )
    (net (code "67") (name "unconnected-(X4-IO5-Pad29)") (class "Default")
      (node (ref "X4") (pin "29") (pinfunction "IO5_29") (pintype "bidirectional"))
    )
    (net (code "68") (name "unconnected-(X4-IO12{slash}A2_5-Pad17)") (class "Default")
      (node (ref "X4") (pin "17") (pinfunction "IO12/A2_5_17") (pintype "bidirectional"))
    )
    (net (code "69") (name "unconnected-(X4-IO15{slash}A2_3-Pad19)") (class "Default")
      (node (ref "X4") (pin "19") (pinfunction "IO15/A2_3_19") (pintype "bidirectional"))
    )
    (net (code "70") (name "unconnected-(X5A-SBU1-PadA8)") (class "Default")
      (node (ref "X5") (pin "A8") (pinfunction "SBU1_A8") (pintype "bidirectional"))
    )
    (net (code "71") (name "unconnected-(X5A-SBU2-PadB8)") (class "Default")
      (node (ref "X5") (pin "B8") (pinfunction "SBU2_B8") (pintype "bidirectional"))
    )
  )
)
